# saturnpad.net
KiCad netlist of a schematic drawn in EAGLE
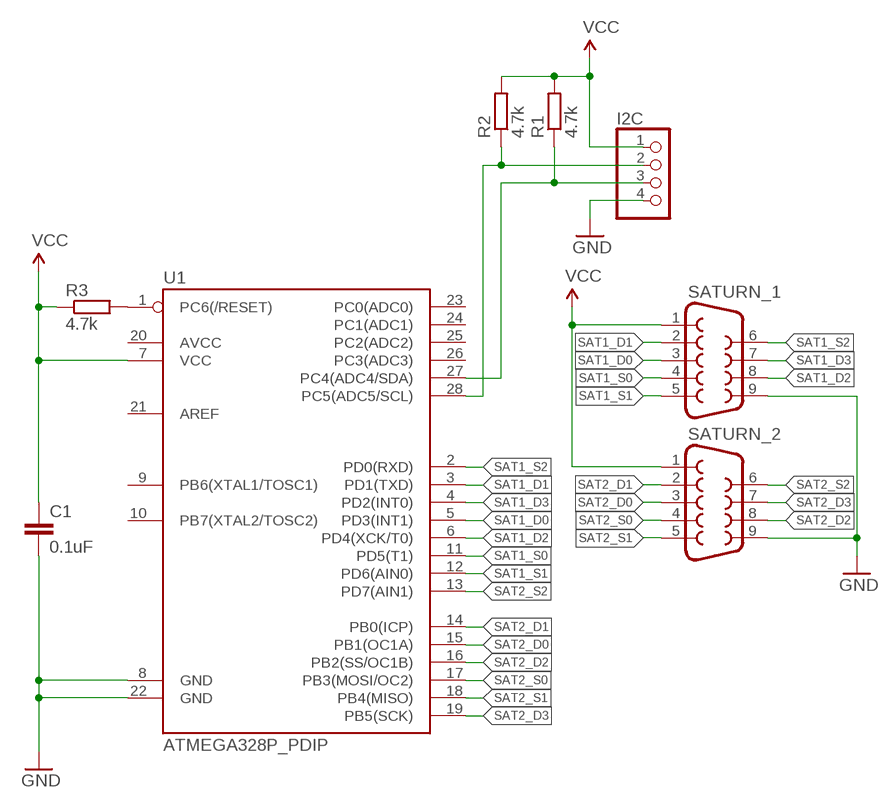
[diagram p0: schematic, sheet 1]

(export (version "E")
  (design (tool "Eeschema 10.0.6"))
  (components
    (comp (ref "C1")
      (value "0.1uF")
      (footprint "eagle-import:C025-030X050")
      (libsource (lib "eagle-import") (part "C-EU025-030X050"))
    )
    (comp (ref "I2C")
      (value "PINHD-1X4/90")
      (footprint "eagle-import:1X04_90")
      (libsource (lib "eagle-import") (part "PINHD-1X4/90"))
    )
    (comp (ref "R1")
      (value "4.7k")
      (footprint "eagle-import:0204_5")
      (libsource (lib "eagle-import") (part "R-EU_0204/5"))
    )
    (comp (ref "R2")
      (value "4.7k")
      (footprint "eagle-import:0204_5")
      (libsource (lib "eagle-import") (part "R-EU_0204/5"))
    )
    (comp (ref "R3")
      (value "4.7k")
      (footprint "eagle-import:0204_5")
      (libsource (lib "eagle-import") (part "R-EU_0204/5"))
    )
    (comp (ref "SATURN_1")
      (value "DB9MALE")
      (footprint "eagle-import:DB9_MALE")
      (libsource (lib "eagle-import") (part "DB9MALE"))
    )
    (comp (ref "SATURN_2")
      (value "DB9MALE")
      (footprint "eagle-import:DB9_MALE")
      (libsource (lib "eagle-import") (part "DB9MALE"))
    )
    (comp (ref "U1")
      (value "ATMEGA328P_PDIP")
      (footprint "eagle-import:DIL28-3")
      (libsource (lib "eagle-import") (part "ATMEGA328P_PDIP"))
    )
  )
  (nets
    (net (code "1") (name "GND") (class "Default")
      (node (ref "C1") (pin "2") (pinfunction "2_2") (pintype "passive"))
      (node (ref "I2C") (pin "4") (pinfunction "4_4") (pintype "passive"))
      (node (ref "SATURN_1") (pin "9") (pinfunction "9_9") (pintype "passive"))
      (node (ref "SATURN_2") (pin "9") (pinfunction "9_9") (pintype "passive"))
      (node (ref "U1") (pin "22") (pinfunction "GND_22") (pintype "bidirectional"))
      (node (ref "U1") (pin "8") (pinfunction "GND_8") (pintype "bidirectional"))
    )
    (net (code "2") (name "Net-(U1-PC4(ADC4{slash}SDA))") (class "Default")
      (node (ref "I2C") (pin "3") (pinfunction "3_3") (pintype "passive"))
      (node (ref "R1") (pin "1") (pinfunction "1_1") (pintype "passive"))
      (node (ref "U1") (pin "27") (pinfunction "PC4(ADC4/SDA)_27") (pintype "bidirectional"))
    )
    (net (code "3") (name "Net-(U1-PC5(ADC5{slash}SCL))") (class "Default")
      (node (ref "I2C") (pin "2") (pinfunction "2_2") (pintype "passive"))
      (node (ref "R2") (pin "1") (pinfunction "1_1") (pintype "passive"))
      (node (ref "U1") (pin "28") (pinfunction "PC5(ADC5/SCL)_28") (pintype "bidirectional"))
    )
    (net (code "4") (name "Net-(U1-PC6({slash}RESET))") (class "Default")
      (node (ref "R3") (pin "2") (pinfunction "2_2") (pintype "passive"))
      (node (ref "U1") (pin "1") (pinfunction "PC6(/RESET)_1") (pintype "bidirectional"))
    )
    (net (code "5") (name "SAT1_D0") (class "Default")
      (node (ref "SATURN_1") (pin "3") (pinfunction "3_3") (pintype "passive"))
      (node (ref "U1") (pin "5") (pinfunction "PD3(INT1)_5") (pintype "bidirectional"))
    )
    (net (code "6") (name "SAT1_D1") (class "Default")
      (node (ref "SATURN_1") (pin "2") (pinfunction "2_2") (pintype "passive"))
      (node (ref "U1") (pin "3") (pinfunction "PD1(TXD)_3") (pintype "bidirectional"))
    )
    (net (code "7") (name "SAT1_D2") (class "Default")
      (node (ref "SATURN_1") (pin "8") (pinfunction "8_8") (pintype "passive"))
      (node (ref "U1") (pin "6") (pinfunction "PD4(XCK/T0)_6") (pintype "bidirectional"))
    )
    (net (code "8") (name "SAT1_D3") (class "Default")
      (node (ref "SATURN_1") (pin "7") (pinfunction "7_7") (pintype "passive"))
      (node (ref "U1") (pin "4") (pinfunction "PD2(INT0)_4") (pintype "bidirectional"))
    )
    (net (code "9") (name "SAT1_S0") (class "Default")
      (node (ref "SATURN_1") (pin "4") (pinfunction "4_4") (pintype "passive"))
      (node (ref "U1") (pin "11") (pinfunction "PD5(T1)_11") (pintype "bidirectional"))
    )
    (net (code "10") (name "SAT1_S1") (class "Default")
      (node (ref "SATURN_1") (pin "5") (pinfunction "5_5") (pintype "passive"))
      (node (ref "U1") (pin "12") (pinfunction "PD6(AIN0)_12") (pintype "bidirectional"))
    )
    (net (code "11") (name "SAT1_S2") (class "Default")
      (node (ref "SATURN_1") (pin "6") (pinfunction "6_6") (pintype "passive"))
      (node (ref "U1") (pin "2") (pinfunction "PD0(RXD)_2") (pintype "bidirectional"))
    )
    (net (code "12") (name "SAT2_D0") (class "Default")
      (node (ref "SATURN_2") (pin "3") (pinfunction "3_3") (pintype "passive"))
      (node (ref "U1") (pin "15") (pinfunction "PB1(OC1A)_15") (pintype "bidirectional"))
    )
    (net (code "13") (name "SAT2_D1") (class "Default")
      (node (ref "SATURN_2") (pin "2") (pinfunction "2_2") (pintype "passive"))
      (node (ref "U1") (pin "14") (pinfunction "PB0(ICP)_14") (pintype "bidirectional"))
    )
    (net (code "14") (name "SAT2_D2") (class "Default")
      (node (ref "SATURN_2") (pin "8") (pinfunction "8_8") (pintype "passive"))
      (node (ref "U1") (pin "16") (pinfunction "PB2(SS/OC1B)_16") (pintype "bidirectional"))
    )
    (net (code "15") (name "SAT2_D3") (class "Default")
      (node (ref "SATURN_2") (pin "7") (pinfunction "7_7") (pintype "passive"))
      (node (ref "U1") (pin "19") (pinfunction "PB5(SCK)_19") (pintype "bidirectional"))
    )
    (net (code "16") (name "SAT2_S0") (class "Default")
      (node (ref "SATURN_2") (pin "4") (pinfunction "4_4") (pintype "passive"))
      (node (ref "U1") (pin "17") (pinfunction "PB3(MOSI/OC2)_17") (pintype "bidirectional"))
    )
    (net (code "17") (name "SAT2_S1") (class "Default")
      (node (ref "SATURN_2") (pin "5") (pinfunction "5_5") (pintype "passive"))
      (node (ref "U1") (pin "18") (pinfunction "PB4(MISO)_18") (pintype "bidirectional"))
    )
    (net (code "18") (name "SAT2_S2") (class "Default")
      (node (ref "SATURN_2") (pin "6") (pinfunction "6_6") (pintype "passive"))
      (node (ref "U1") (pin "13") (pinfunction "PD7(AIN1)_13") (pintype "bidirectional"))
    )
    (net (code "19") (name "VCC") (class "Default")
      (node (ref "C1") (pin "1") (pinfunction "1_1") (pintype "passive"))
      (node (ref "I2C") (pin "1") (pinfunction "1_1") (pintype "passive"))
      (node (ref "R1") (pin "2") (pinfunction "2_2") (pintype "passive"))
      (node (ref "R2") (pin "2") (pinfunction "2_2") (pintype "passive"))
      (node (ref "R3") (pin "1") (pinfunction "1_1") (pintype "passive"))
      (node (ref "SATURN_1") (pin "1") (pinfunction "1_1") (pintype "passive"))
      (node (ref "SATURN_2") (pin "1") (pinfunction "1_1") (pintype "passive"))
      (node (ref "U1") (pin "7") (pinfunction "VCC_7") (pintype "bidirectional"))
    )
    (net (code "20") (name "unconnected-(U1-AREF-Pad21)") (class "Default")
      (node (ref "U1") (pin "21") (pinfunction "AREF_21") (pintype "bidirectional"))
    )
    (net (code "21") (name "unconnected-(U1-AVCC-Pad20)") (class "Default")
      (node (ref "U1") (pin "20") (pinfunction "AVCC_20") (pintype "bidirectional"))
    )
    (net (code "22") (name "unconnected-(U1-PB6(XTAL1{slash}TOSC1)-Pad9)") (class "Default")
      (node (ref "U1") (pin "9") (pinfunction "PB6(XTAL1/TOSC1)_9") (pintype "bidirectional"))
    )
    (net (code "23") (name "unconnected-(U1-PB7(XTAL2{slash}TOSC2)-Pad10)") (class "Default")
      (node (ref "U1") (pin "10") (pinfunction "PB7(XTAL2/TOSC2)_10") (pintype "bidirectional"))
    )
    (net (code "24") (name "unconnected-(U1-PC0(ADC0)-Pad23)") (class "Default")
      (node (ref "U1") (pin "23") (pinfunction "PC0(ADC0)_23") (pintype "bidirectional"))
    )
    (net (code "25") (name "unconnected-(U1-PC1(ADC1)-Pad24)") (class "Default")
      (node (ref "U1") (pin "24") (pinfunction "PC1(ADC1)_24") (pintype "bidirectional"))
    )
    (net (code "26") (name "unconnected-(U1-PC2(ADC2)-Pad25)") (class "Default")
      (node (ref "U1") (pin "25") (pinfunction "PC2(ADC2)_25") (pintype "bidirectional"))
    )
    (net (code "27") (name "unconnected-(U1-PC3(ADC3)-Pad26)") (class "Default")
      (node (ref "U1") (pin "26") (pinfunction "PC3(ADC3)_26") (pintype "bidirectional"))
    )
  )
)
